# MODULIQ_POE_SPI.net
KiCad netlist of a schematic drawn in Altium Designer
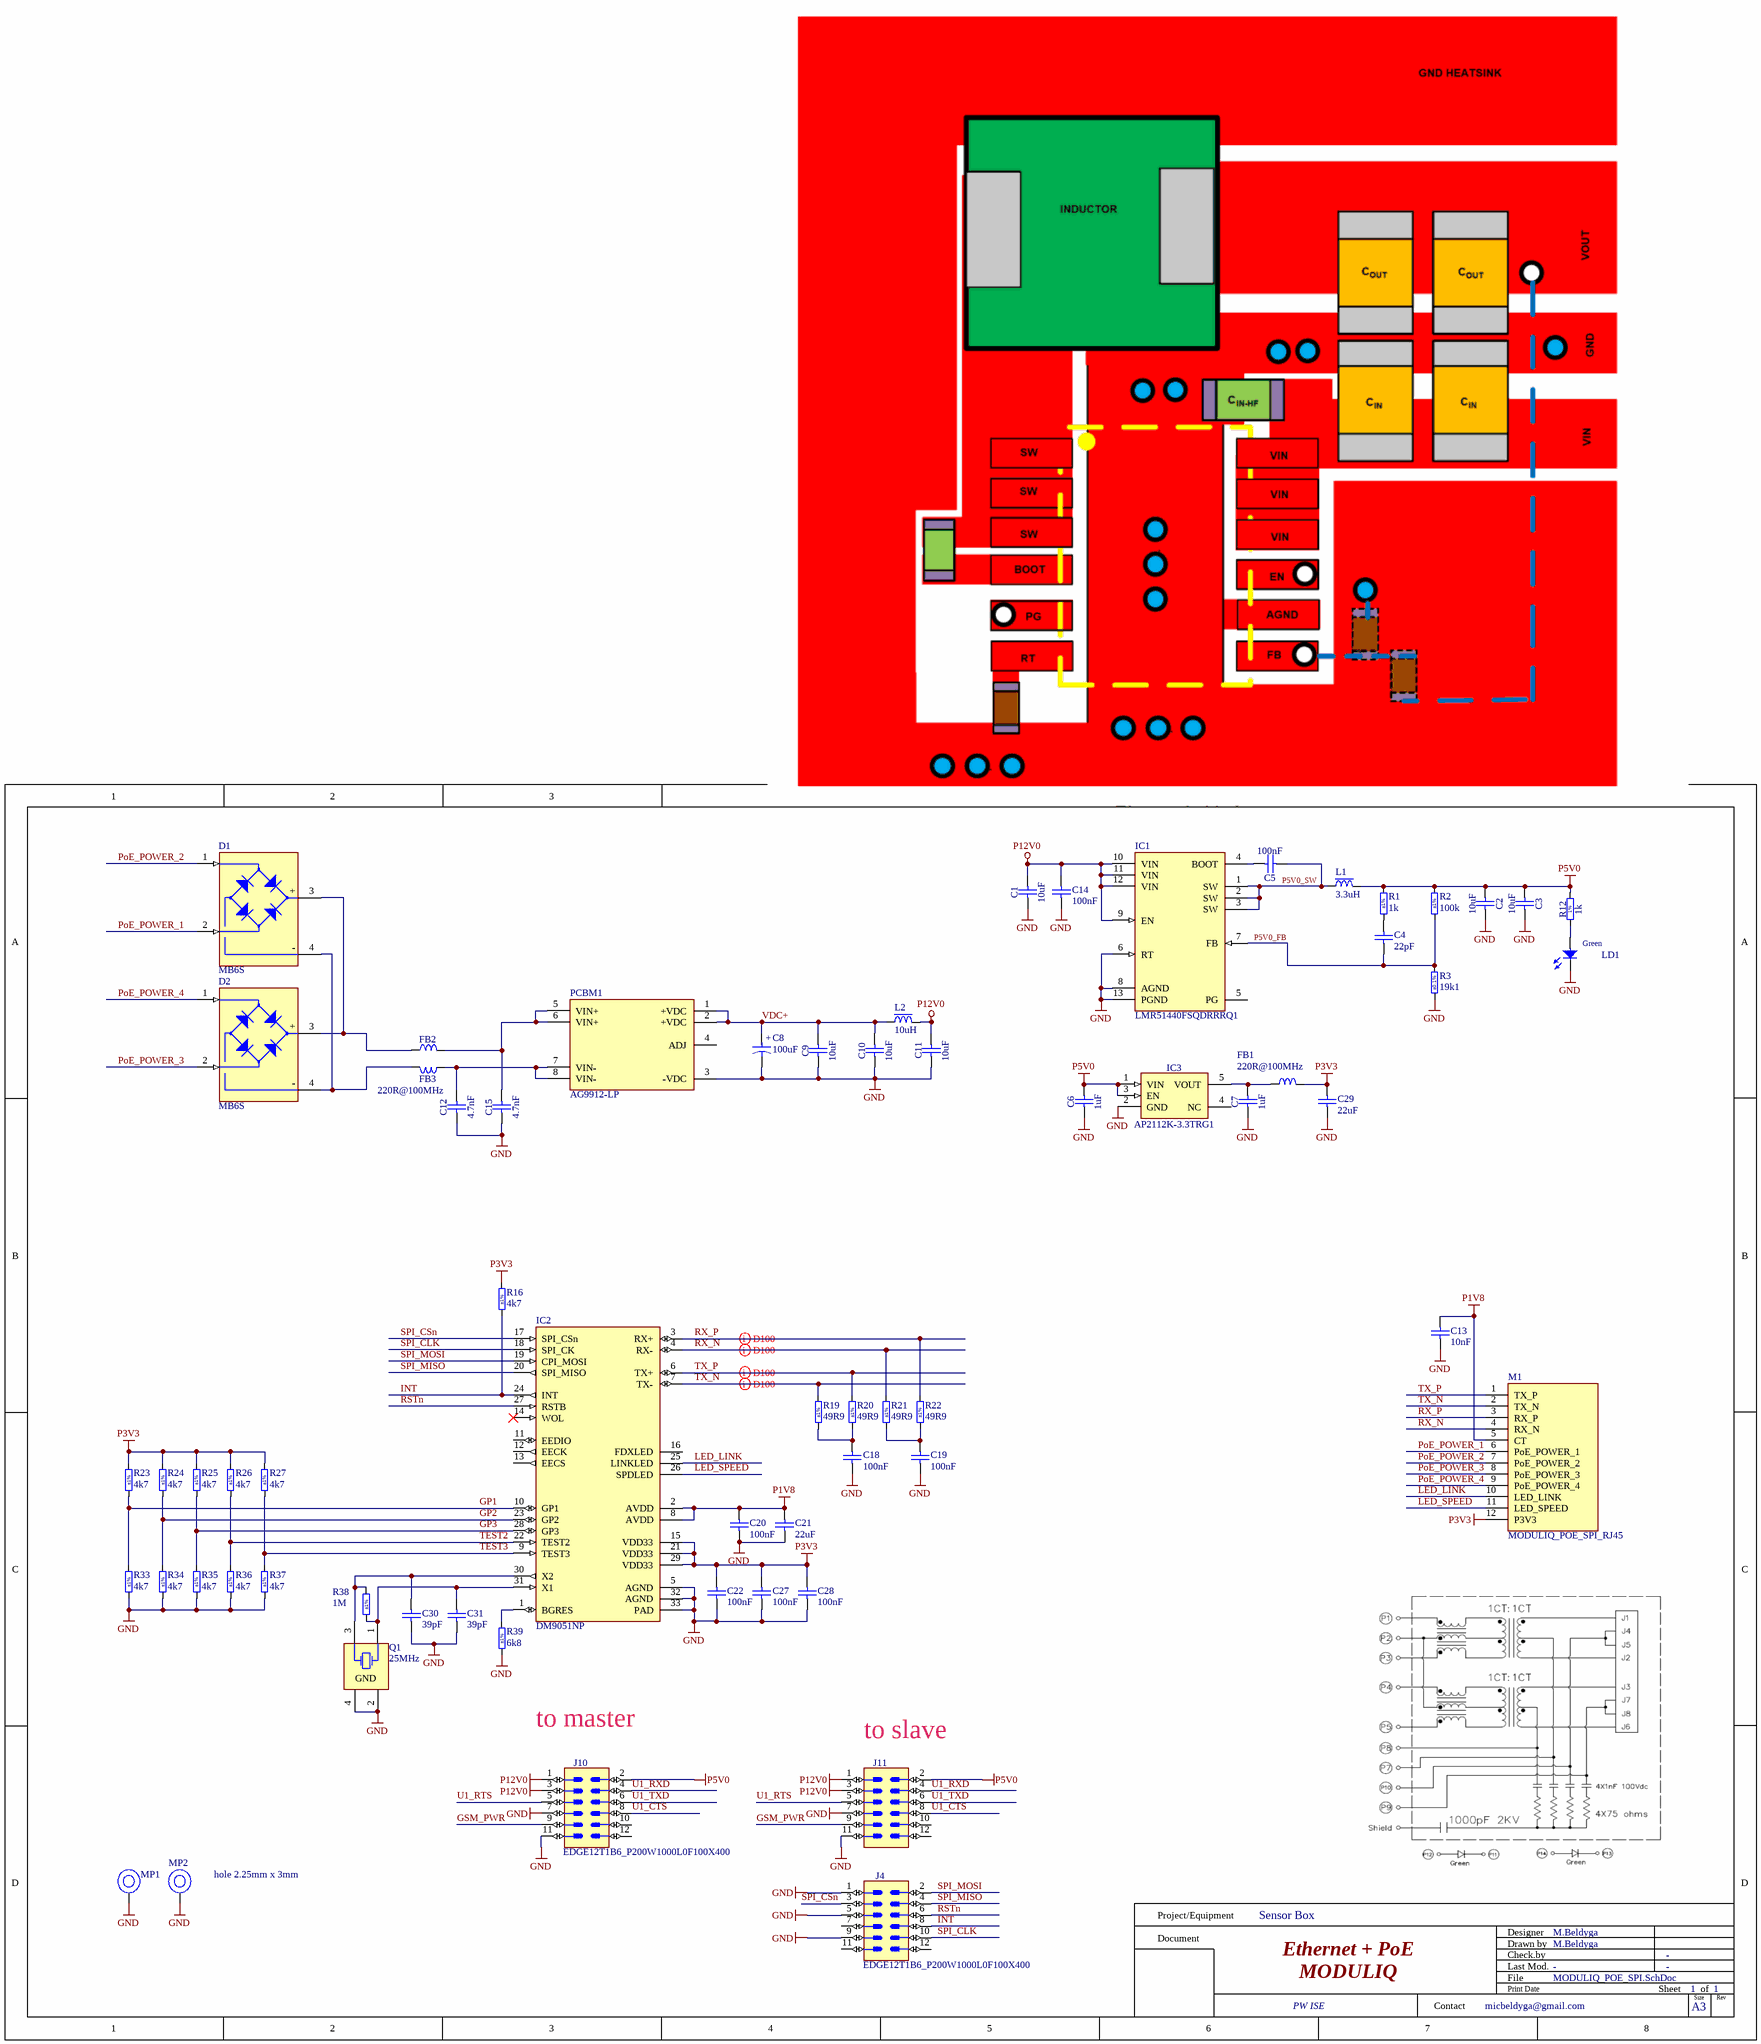
[diagram p0: MODULIQ_POE_SPI.SchDoc]

(export (version "E")
  (design (tool "Eeschema 10.0.6"))
  (components
    (comp (ref "C1")
      (value "10uF")
      (footprint "CAPC2012X135N")
      (description "Non-polarised capacitor")
      (fields
        (field (name "PART NUMBER") "CC0805_10UF_16V_10%_X5R")
        (field (name "VOLTAGE") "16V")
        (field (name "AUTHOR") "CERN DEM JLC")
      )
      (libsource (lib "Capacitors") (part "Capacitor - non polarized"))
    )
    (comp (ref "C2")
      (value "10uF")
      (footprint "CAPC2012X135N")
      (description "Non-polarised capacitor")
      (fields
        (field (name "PART NUMBER") "CC0805_10UF_16V_10%_X5R")
        (field (name "VOLTAGE") "16V")
        (field (name "AUTHOR") "CERN DEM JLC")
      )
      (libsource (lib "Capacitors") (part "Capacitor - non polarized"))
    )
    (comp (ref "C3")
      (value "10uF")
      (footprint "CAPC2012X135N")
      (description "Non-polarised capacitor")
      (fields
        (field (name "PART NUMBER") "CC0805_10UF_16V_10%_X5R")
        (field (name "VOLTAGE") "16V")
        (field (name "AUTHOR") "CERN DEM JLC")
      )
      (libsource (lib "Capacitors") (part "Capacitor - non polarized"))
    )
    (comp (ref "C4")
      (value "22pF")
      (footprint "CAPC1005X55N")
      (description "Non-polarised capacitor")
      (fields
        (field (name "PART NUMBER") "CC0402_22PF_50V_5%_C0G")
        (field (name "VOLTAGE") "50V")
        (field (name "AUTHOR") "CERN DEM JLC")
      )
      (libsource (lib "Capacitors") (part "Capacitor - non polarized"))
    )
    (comp (ref "C5")
      (value "100nF")
      (footprint "CAPC1005X55N")
      (description "Non-polarised capacitor")
      (fields
        (field (name "PART NUMBER") "CC0402_100NF_16V_10%_X5R")
        (field (name "VOLTAGE") "16V")
        (field (name "AUTHOR") "CERN DEM JLC")
      )
      (libsource (lib "Capacitors") (part "Capacitor - non polarized"))
    )
    (comp (ref "C6")
      (value "1uF")
      (footprint "CAPC1005X55N")
      (description "Non-polarised capacitor")
      (fields
        (field (name "PART NUMBER") "CC0402_1UF_16V_10%_X5R")
        (field (name "VOLTAGE") "16V")
        (field (name "AUTHOR") "CERN DEM JLC")
      )
      (libsource (lib "Capacitors") (part "Capacitor - non polarized"))
    )
    (comp (ref "C7")
      (value "1uF")
      (footprint "CAPC1005X55N")
      (description "Non-polarised capacitor")
      (fields
        (field (name "PART NUMBER") "CC0402_1UF_16V_10%_X5R")
        (field (name "VOLTAGE") "16V")
        (field (name "AUTHOR") "CERN DEM JLC")
      )
      (libsource (lib "Capacitors") (part "Capacitor - non polarized"))
    )
    (comp (ref "C8")
      (value "100uF")
      (footprint "CAPMP7343X430N")
      (description "Polarised capacitor")
      (fields
        (field (name "PART NUMBER") "CTE7343-43_100UF_25V_10%_LESR0150")
        (field (name "VOLTAGE") "25V")
        (field (name "AUTHOR") "CERN DEM JLC")
      )
      (libsource (lib "Capacitors") (part "Capacitor - polarized"))
    )
    (comp (ref "C9")
      (value "10uF")
      (footprint "CAPC2012X135N")
      (description "Non-polarised capacitor")
      (fields
        (field (name "PART NUMBER") "CC0805_10UF_16V_10%_X5R")
        (field (name "VOLTAGE") "16V")
        (field (name "AUTHOR") "CERN DEM JLC")
      )
      (libsource (lib "Capacitors") (part "Capacitor - non polarized"))
    )
    (comp (ref "C10")
      (value "10uF")
      (footprint "CAPC2012X135N")
      (description "Non-polarised capacitor")
      (fields
        (field (name "PART NUMBER") "CC0805_10UF_16V_10%_X5R")
        (field (name "VOLTAGE") "16V")
        (field (name "AUTHOR") "CERN DEM JLC")
      )
      (libsource (lib "Capacitors") (part "Capacitor - non polarized"))
    )
    (comp (ref "C11")
      (value "10uF")
      (footprint "CAPC2012X135N")
      (description "Non-polarised capacitor")
      (fields
        (field (name "PART NUMBER") "CC0805_10UF_16V_10%_X5R")
        (field (name "VOLTAGE") "16V")
        (field (name "AUTHOR") "CERN DEM JLC")
      )
      (libsource (lib "Capacitors") (part "Capacitor - non polarized"))
    )
    (comp (ref "C12")
      (value "4.7nF")
      (footprint "CAPC3216X140N")
      (description "Non-polarised capacitor")
      (fields
        (field (name "PART NUMBER") "CC1206_4.7NF_500V_10%_X7R")
        (field (name "VOLTAGE") "500V")
        (field (name "AUTHOR") "GK")
      )
      (libsource (lib "LIBRARY_SCH") (part "CAP_SMD_1206_4.7n_500V"))
    )
    (comp (ref "C13")
      (value "10nF")
      (footprint "CAPC1608X87N")
      (description "Non-polarised capacitor")
      (fields
        (field (name "PART NUMBER") "CC0603_10NF_50V_5%_C0G")
        (field (name "VOLTAGE") "50V")
        (field (name "AUTHOR") "CERN DEM JLC")
      )
      (libsource (lib "Capacitors") (part "Capacitor - non polarized"))
    )
    (comp (ref "C14")
      (value "100nF")
      (footprint "CAPC1005X55N")
      (description "Non-polarised capacitor")
      (fields
        (field (name "PART NUMBER") "CC0402_100NF_16V_10%_X5R")
        (field (name "VOLTAGE") "16V")
        (field (name "AUTHOR") "CERN DEM JLC")
      )
      (libsource (lib "Capacitors") (part "Capacitor - non polarized"))
    )
    (comp (ref "C15")
      (value "4.7nF")
      (footprint "CAPC3216X140N")
      (description "Non-polarised capacitor")
      (fields
        (field (name "PART NUMBER") "CC1206_4.7NF_500V_10%_X7R")
        (field (name "VOLTAGE") "500V")
        (field (name "AUTHOR") "GK")
      )
      (libsource (lib "LIBRARY_SCH") (part "CAP_SMD_1206_4.7n_500V"))
    )
    (comp (ref "C18")
      (value "100nF")
      (footprint "CAPC1005X55N")
      (description "Non-polarised capacitor")
      (fields
        (field (name "PART NUMBER") "CC0402_100NF_16V_10%_X5R")
        (field (name "VOLTAGE") "16V")
        (field (name "AUTHOR") "CERN DEM JLC")
      )
      (libsource (lib "Capacitors") (part "Capacitor - non polarized"))
    )
    (comp (ref "C19")
      (value "100nF")
      (footprint "CAPC1005X55N")
      (description "Non-polarised capacitor")
      (fields
        (field (name "PART NUMBER") "CC0402_100NF_16V_10%_X5R")
        (field (name "VOLTAGE") "16V")
        (field (name "AUTHOR") "CERN DEM JLC")
      )
      (libsource (lib "Capacitors") (part "Capacitor - non polarized"))
    )
    (comp (ref "C20")
      (value "100nF")
      (footprint "CAPC1005X55N")
      (description "Non-polarised capacitor")
      (fields
        (field (name "PART NUMBER") "CC0402_100NF_16V_10%_X5R")
        (field (name "VOLTAGE") "16V")
        (field (name "AUTHOR") "CERN DEM JLC")
      )
      (libsource (lib "Capacitors") (part "Capacitor - non polarized"))
    )
    (comp (ref "C21")
      (value "22uF")
      (footprint "CAPC1005X70N")
      (description "Non-polarised capacitor")
      (fields
        (field (name "PART NUMBER") "CC0402_22UF_6.3V_20%_X5R")
        (field (name "VOLTAGE") "6.3V")
        (field (name "AUTHOR") "CERN DEM HF")
      )
      (libsource (lib "Capacitors") (part "Capacitor - non polarized"))
    )
    (comp (ref "C22")
      (value "100nF")
      (footprint "CAPC1005X55N")
      (description "Non-polarised capacitor")
      (fields
        (field (name "PART NUMBER") "CC0402_100NF_16V_10%_X5R")
        (field (name "VOLTAGE") "16V")
        (field (name "AUTHOR") "CERN DEM JLC")
      )
      (libsource (lib "Capacitors") (part "Capacitor - non polarized"))
    )
    (comp (ref "C27")
      (value "100nF")
      (footprint "CAPC1005X55N")
      (description "Non-polarised capacitor")
      (fields
        (field (name "PART NUMBER") "CC0402_100NF_16V_10%_X5R")
        (field (name "VOLTAGE") "16V")
        (field (name "AUTHOR") "CERN DEM JLC")
      )
      (libsource (lib "Capacitors") (part "Capacitor - non polarized"))
    )
    (comp (ref "C28")
      (value "100nF")
      (footprint "CAPC1005X55N")
      (description "Non-polarised capacitor")
      (fields
        (field (name "PART NUMBER") "CC0402_100NF_16V_10%_X5R")
        (field (name "VOLTAGE") "16V")
        (field (name "AUTHOR") "CERN DEM JLC")
      )
      (libsource (lib "Capacitors") (part "Capacitor - non polarized"))
    )
    (comp (ref "C29")
      (value "22uF")
      (footprint "CAPC1005X70N")
      (description "Non-polarised capacitor")
      (fields
        (field (name "PART NUMBER") "CC0402_22UF_6.3V_20%_X5R")
        (field (name "VOLTAGE") "6.3V")
        (field (name "AUTHOR") "CERN DEM HF")
      )
      (libsource (lib "Capacitors") (part "Capacitor - non polarized"))
    )
    (comp (ref "C30")
      (value "39pF")
      (footprint "CAPC1005X55N")
      (description "Non-polarised capacitor")
      (fields
        (field (name "PART NUMBER") "CC0402_39PF_100V_5%_C0G_MURATA_GRM1555C2A390JA01")
        (field (name "VOLTAGE") "100V")
        (field (name "AUTHOR") "CERN DEM BC")
      )
      (libsource (lib "Capacitors") (part "Capacitor - non polarized"))
    )
    (comp (ref "C31")
      (value "39pF")
      (footprint "CAPC1005X55N")
      (description "Non-polarised capacitor")
      (fields
        (field (name "PART NUMBER") "CC0402_39PF_100V_5%_C0G_MURATA_GRM1555C2A390JA01")
        (field (name "VOLTAGE") "100V")
        (field (name "AUTHOR") "CERN DEM BC")
      )
      (libsource (lib "Capacitors") (part "Capacitor - non polarized"))
    )
    (comp (ref "D1")
      (value "MB6S")
      (footprint "SOIC254P665X290-4N")
      (description "Bridge Rectifier 1AC 2AC 3+ 4-")
      (fields
        (field (name "VOLTAGE") "600V")
        (field (name "POWER") "0.5A")
        (field (name "AUTHOR") "CERN DEM MR")
      )
      (libsource (lib "ICs And Semiconductors") (part "Bridge Rectifier 1AC 2AC 3+ 4-"))
    )
    (comp (ref "D2")
      (value "MB6S")
      (footprint "SOIC254P665X290-4N")
      (description "Bridge Rectifier 1AC 2AC 3+ 4-")
      (fields
        (field (name "VOLTAGE") "600V")
        (field (name "POWER") "0.5A")
        (field (name "AUTHOR") "CERN DEM MR")
      )
      (libsource (lib "ICs And Semiconductors") (part "Bridge Rectifier 1AC 2AC 3+ 4-"))
    )
    (comp (ref "FB1")
      (value "220R@100MHz")
      (footprint "INDC2012X105N")
      (description "Inductor")
      (fields
        (field (name "PART NUMBER") "IND0805_MURATA_BLM21PG221SN1D")
        (field (name "POWER") "2A")
        (field (name "AUTHOR") "CERN DEM JLC")
      )
      (libsource (lib "") (part "Inductor_1"))
    )
    (comp (ref "FB2")
      (value "220R@100MHz")
      (footprint "INDC2012X105N")
      (description "Inductor")
      (fields
        (field (name "PART NUMBER") "IND0805_MURATA_BLM21PG221SN1D")
        (field (name "POWER") "2A")
        (field (name "AUTHOR") "CERN DEM JLC")
      )
      (libsource (lib "Inductors & Transformers") (part "Inductor"))
    )
    (comp (ref "FB3")
      (value "220R@100MHz")
      (footprint "INDC2012X105N")
      (description "Inductor")
      (fields
        (field (name "PART NUMBER") "IND0805_MURATA_BLM21PG221SN1D")
        (field (name "POWER") "2A")
        (field (name "AUTHOR") "CERN DEM JLC")
      )
      (libsource (lib "") (part "Inductor_1"))
    )
    (comp (ref "IC1")
      (value "LMR51440FSQDRRRQ1")
      (footprint "SON50P300X80_HS-13N")
      (description "LMR51440-Q1 36V, 4A, Automotive, Synchronous Buck Converter With Low IQ")
      (fields
        (field (name "MANUFACTURER") "Texas Instruments")
        (field (name "ARENA PART NUMBER") "150-000055")
        (field (name "AUTHOR") "Michal Beldyga")
      )
      (libsource (lib "Semiconductors") (part "LMR514x0"))
    )
    (comp (ref "IC2")
      (value "DM9051NP")
      (footprint "QFN50P500X500X90_HS-33N_DM9051")
      (libsource (lib "mb") (part "DM9051NP"))
    )
    (comp (ref "IC3")
      (value "AP2112K-3.3TRG1")
      (footprint "SOT95P285X140-5N")
      (description "600mA CMOS Low Dropout Linear Regulator with Enable")
      (fields
        (field (name "MANUFACTURER") "DIODES INCORPORATED")
        (field (name "MANUFACTURER PART NUMBER") "AP2112K-3.3")
        (field (name "AUTHOR") "CERN DEM MR")
      )
      (libsource (lib "ICs And Semiconductors") (part "AP2112K"))
    )
    (comp (ref "J4")
      (value "~")
      (footprint "EDGE12T1B6_P200W1000L0F100X400")
      (description "PCB Edge Connector 12 (2x6)")
      (fields
        (field (name "PART NUMBER") "EDGE10T1B6_P200W1000L0F100X400")
        (field (name "AUTHOR") "CERN DEM MR")
      )
      (libsource (lib "Connectors") (part "PCB Edge Connector 12 (2x6)"))
    )
    (comp (ref "J10")
      (value "~")
      (footprint "EDGE12T1B6_P200W1000L0F100X400")
      (description "PCB Edge Connector 12 (2x6)")
      (fields
        (field (name "PART NUMBER") "EDGE10T1B6_P200W1000L0F100X400")
        (field (name "AUTHOR") "CERN DEM MR")
      )
      (libsource (lib "Connectors") (part "PCB Edge Connector 12 (2x6)"))
    )
    (comp (ref "J11")
      (value "~")
      (footprint "EDGE12T5B10_P200W1000L0F100X400")
      (description "PCB Edge Connector 12 (2x6)")
      (fields (field (name "PART NUMBER") "EDGE12T5B10_P200W1000L0F100X400") (field (name "AUTHOR") "GK"))
      (libsource (lib "Connectors") (part "PCB Edge Connector 12 (2x6) R"))
    )
    (comp (ref "L1")
      (value "3.3uH")
      (footprint "IND_COILCRAFT_XAL4030")
      (description "Inductor With Core")
      (fields
        (field (name "PART NUMBER") "IND_3.3UH_20%_COILCRAFT_XAL4030")
        (field (name "POWER") "5A")
        (field (name "AUTHOR") "CERN DEM BC")
      )
      (libsource (lib "Inductors & Transformers") (part "Inductor With Magnetic core"))
    )
    (comp (ref "L2")
      (value "10uH")
      (footprint "IND_MURATA-PS_8400")
      (description "Inductor With Core")
      (fields
        (field (name "PART NUMBER") "IND_10UH_10%_MURATA-PS_8400")
        (field (name "POWER") "950mA")
        (field (name "AUTHOR") "CERN DEM JLC")
      )
      (libsource (lib "Inductors & Transformers") (part "Inductor With Magnetic core"))
    )
    (comp (ref "LD1")
      (value "Green")
      (footprint "LED_KINGBRIGHT_KP-1608CGCK")
      (description "LED Green 1C 2A")
      (fields
        (field (name "PART NUMBER") "LED_KINGBRIGHT_KP-1608CGCK")
        (field (name "MANUFACTURER") "KINGBRIGHT")
        (field (name "AUTHOR") "CERN DEM HF")
      )
      (libsource (lib "ICs And Semiconductors") (part "LED Green 1C 2A"))
    )
    (comp (ref "M1")
      (value "MODULIQ_POE_SPI_RJ45")
      (footprint "MODULIQ_POE_SPI_RJ45")
      (description "MODULIQ POE SPI RJ45 module")
      (libsource (lib "mb") (part "MODULIQ_POE_SPI_RJ45"))
    )
    (comp (ref "MP1")
      (value "M1.6 x 3mm")
      (footprint "97730306330")
      (description "WA-SMSI SMT Steel Spacer with internal Thread Bottom closed, OD 3.3mm, M1.6 x 3mm")
      (fields
        (field (name "MANUFACTURER PART NUMBER") "97730306330R")
        (field (name "MANUFACTURER") "Wurth Elektronik")
      )
      (libsource (lib "Altium_WA-SMSI (rev22a)") (part "97730306330R"))
    )
    (comp (ref "MP2")
      (value "hole 2.25mm x 3mm")
      (footprint "9774030943")
      (description "WA-SMST SMT Steel Spacer, OD 4.35mm, hole 2.25mm x 3mm")
      (fields
        (field (name "MANUFACTURER PART NUMBER") "9774030943R")
        (field (name "MANUFACTURER") "Wurth Elektronik")
      )
      (libsource (lib "WE - Electromechanical Components") (part "Spacer"))
    )
    (comp (ref "PCBM1")
      (value "AG9912-LP")
      (footprint "Ag9900LP")
      (description "Low Profile IEEE802.3 af PoE Module - 12V")
      (fields (field (name "MANUFACTURER") "Silvertel"))
      (libsource (lib "mb") (part "AG9912-LP"))
    )
    (comp (ref "Q1")
      (value "25MHz")
      (footprint "XTAL_EPSON_TSX-3225")
      (description "Crystal 4 pins 1=XTAL Control 2=GND3=XTAL 4=GND")
      (fields
        (field (name "PART NUMBER") "XTAL_25MHZ_EPSON_TSX-3225 25.0000MF10Z-AC")
        (field (name "MANUFACTURER") "EPSON")
        (field (name "AUTHOR") "CERN DEM JLC")
      )
      (libsource (lib "ICs And Semiconductors") (part "Quartz Crystal 1X 2GND 3X 4GND"))
    )
    (comp (ref "R1")
      (value "1k")
      (footprint "RESC1005X40N")
      (description "Resistor - 1%")
      (fields
        (field (name "TOLERANCE") "±1%")
        (field (name "PART NUMBER") "R0402_1K_1%_0.0625W_100PPM")
        (field (name "POWER") "0.0625W")
        (field (name "AUTHOR") "CERN DEM JLC")
      )
      (libsource (lib "Resistors") (part "Resistor - 1%"))
    )
    (comp (ref "R2")
      (value "100k")
      (footprint "RESC1005X40N")
      (description "Resistor - 1%")
      (fields
        (field (name "TOLERANCE") "±1%")
        (field (name "PART NUMBER") "R0402_100K_1%_0.0625W_100PPM")
        (field (name "POWER") "0.0625W")
        (field (name "AUTHOR") "CERN DEM JLC")
      )
      (libsource (lib "Resistors") (part "Resistor - 1%"))
    )
    (comp (ref "R3")
      (value "19k1")
      (footprint "RESC1005X35N")
      (description "Resistor - 0.1%")
      (fields
        (field (name "TOLERANCE") "±0.1%")
        (field (name "PART NUMBER") "R0402_19K1_0.1%_0.063W_25PPM")
        (field (name "POWER") "0.063W")
        (field (name "AUTHOR") "CERN DEM MR")
      )
      (libsource (lib "Resistors") (part "Resistor - 0.1%"))
    )
    (comp (ref "R12")
      (value "1k")
      (footprint "RESC1005X40N")
      (description "Resistor - 1%")
      (fields
        (field (name "PART NUMBER") "R0402_1K_1%_0.0625W_100PPM")
        (field (name "POWER") "0.0625W")
        (field (name "AUTHOR") "CERN DEM JLC")
      )
      (libsource (lib "Resistors") (part "Resistor - 1%"))
    )
    (comp (ref "R16")
      (value "4k7")
      (footprint "RESC1005X40N")
      (description "Resistor - 1%")
      (fields
        (field (name "TOLERANCE") "±1%")
        (field (name "PART NUMBER") "R0402_4K7_1%_0.0625W_100PPM")
        (field (name "POWER") "0.0625W")
        (field (name "AUTHOR") "CERN DEM JLC")
      )
      (libsource (lib "Resistors") (part "Resistor - 1%"))
    )
    (comp (ref "R19")
      (value "49R9")
      (footprint "RESC1005X40N")
      (description "Resistor - 1%")
      (fields
        (field (name "TOLERANCE") "±1%")
        (field (name "PART NUMBER") "R0402_49R9_1%_0.0625W_100PPM")
        (field (name "POWER") "0.0625W")
        (field (name "AUTHOR") "CERN DEM JLC")
      )
      (libsource (lib "Resistors") (part "Resistor - 1%"))
    )
    (comp (ref "R20")
      (value "49R9")
      (footprint "RESC1005X40N")
      (description "Resistor - 1%")
      (fields
        (field (name "TOLERANCE") "±1%")
        (field (name "PART NUMBER") "R0402_49R9_1%_0.0625W_100PPM")
        (field (name "POWER") "0.0625W")
        (field (name "AUTHOR") "CERN DEM JLC")
      )
      (libsource (lib "Resistors") (part "Resistor - 1%"))
    )
    (comp (ref "R21")
      (value "49R9")
      (footprint "RESC1005X40N")
      (description "Resistor - 1%")
      (fields
        (field (name "TOLERANCE") "±1%")
        (field (name "PART NUMBER") "R0402_49R9_1%_0.0625W_100PPM")
        (field (name "POWER") "0.0625W")
        (field (name "AUTHOR") "CERN DEM JLC")
      )
      (libsource (lib "Resistors") (part "Resistor - 1%"))
    )
    (comp (ref "R22")
      (value "49R9")
      (footprint "RESC1005X40N")
      (description "Resistor - 1%")
      (fields
        (field (name "TOLERANCE") "±1%")
        (field (name "PART NUMBER") "R0402_49R9_1%_0.0625W_100PPM")
        (field (name "POWER") "0.0625W")
        (field (name "AUTHOR") "CERN DEM JLC")
      )
      (libsource (lib "Resistors") (part "Resistor - 1%"))
    )
    (comp (ref "R23")
      (value "4k7")
      (footprint "RESC1005X40N")
      (description "Resistor - 1%")
      (fields
        (field (name "TOLERANCE") "±1%")
        (field (name "PART NUMBER") "R0402_4K7_1%_0.0625W_100PPM")
        (field (name "POWER") "0.0625W")
        (field (name "AUTHOR") "CERN DEM JLC")
      )
      (libsource (lib "Resistors") (part "Resistor - 1%"))
    )
    (comp (ref "R24")
      (value "4k7")
      (footprint "RESC1005X40N")
      (description "Resistor - 1%")
      (fields
        (field (name "TOLERANCE") "±1%")
        (field (name "PART NUMBER") "R0402_4K7_1%_0.0625W_100PPM")
        (field (name "POWER") "0.0625W")
        (field (name "AUTHOR") "CERN DEM JLC")
      )
      (libsource (lib "Resistors") (part "Resistor - 1%"))
    )
    (comp (ref "R25")
      (value "4k7")
      (footprint "RESC1005X40N")
      (description "Resistor - 1%")
      (fields
        (field (name "TOLERANCE") "±1%")
        (field (name "PART NUMBER") "R0402_4K7_1%_0.0625W_100PPM")
        (field (name "POWER") "0.0625W")
        (field (name "AUTHOR") "CERN DEM JLC")
      )
      (libsource (lib "Resistors") (part "Resistor - 1%"))
    )
    (comp (ref "R26")
      (value "4k7")
      (footprint "RESC1005X40N")
      (description "Resistor - 1%")
      (fields
        (field (name "TOLERANCE") "±1%")
        (field (name "PART NUMBER") "R0402_4K7_1%_0.0625W_100PPM")
        (field (name "POWER") "0.0625W")
        (field (name "AUTHOR") "CERN DEM JLC")
      )
      (libsource (lib "Resistors") (part "Resistor - 1%"))
    )
    (comp (ref "R27")
      (value "4k7")
      (footprint "RESC1005X40N")
      (description "Resistor - 1%")
      (fields
        (field (name "TOLERANCE") "±1%")
        (field (name "PART NUMBER") "R0402_4K7_1%_0.0625W_100PPM")
        (field (name "POWER") "0.0625W")
        (field (name "AUTHOR") "CERN DEM JLC")
      )
      (libsource (lib "Resistors") (part "Resistor - 1%"))
    )
    (comp (ref "R33")
      (value "4k7")
      (footprint "RESC1005X40N")
      (description "Resistor - 1%")
      (fields
        (field (name "TOLERANCE") "±1%")
        (field (name "PART NUMBER") "R0402_4K7_1%_0.0625W_100PPM")
        (field (name "POWER") "0.0625W")
        (field (name "AUTHOR") "CERN DEM JLC")
      )
      (libsource (lib "Resistors") (part "Resistor - 1%"))
    )
    (comp (ref "R34")
      (value "4k7")
      (footprint "RESC1005X40N")
      (description "Resistor - 1%")
      (fields
        (field (name "TOLERANCE") "±1%")
        (field (name "PART NUMBER") "R0402_4K7_1%_0.0625W_100PPM")
        (field (name "POWER") "0.0625W")
        (field (name "AUTHOR") "CERN DEM JLC")
      )
      (libsource (lib "Resistors") (part "Resistor - 1%"))
    )
    (comp (ref "R35")
      (value "4k7")
      (footprint "RESC1005X40N")
      (description "Resistor - 1%")
      (fields
        (field (name "TOLERANCE") "±1%")
        (field (name "PART NUMBER") "R0402_4K7_1%_0.0625W_100PPM")
        (field (name "POWER") "0.0625W")
        (field (name "AUTHOR") "CERN DEM JLC")
      )
      (libsource (lib "Resistors") (part "Resistor - 1%"))
    )
    (comp (ref "R36")
      (value "4k7")
      (footprint "RESC1005X40N")
      (description "Resistor - 1%")
      (fields
        (field (name "TOLERANCE") "±1%")
        (field (name "PART NUMBER") "R0402_4K7_1%_0.0625W_100PPM")
        (field (name "POWER") "0.0625W")
        (field (name "AUTHOR") "CERN DEM JLC")
      )
      (libsource (lib "Resistors") (part "Resistor - 1%"))
    )
    (comp (ref "R37")
      (value "4k7")
      (footprint "RESC1005X40N")
      (description "Resistor - 1%")
      (fields
        (field (name "TOLERANCE") "±1%")
        (field (name "PART NUMBER") "R0402_4K7_1%_0.0625W_100PPM")
        (field (name "POWER") "0.0625W")
        (field (name "AUTHOR") "CERN DEM JLC")
      )
      (libsource (lib "Resistors") (part "Resistor - 1%"))
    )
    (comp (ref "R38")
      (value "1M")
      (footprint "RESC1005X40N")
      (description "Resistor - 1%")
      (fields
        (field (name "TOLERANCE") "±1%")
        (field (name "PART NUMBER") "R0402_1M_1%_0.0625W_100PPM")
        (field (name "POWER") "0.0625W")
        (field (name "AUTHOR") "CERN DEM JLC")
      )
      (libsource (lib "Resistors") (part "Resistor - 1%"))
    )
    (comp (ref "R39")
      (value "6k8")
      (footprint "RESC1005X40N")
      (description "Resistor - 1%")
      (fields
        (field (name "TOLERANCE") "±1%")
        (field (name "PART NUMBER") "R0402_6K8_1%_0.0625W_100PPM")
        (field (name "POWER") "0.0625W")
        (field (name "AUTHOR") "CERN DEM JLC")
      )
      (libsource (lib "Resistors") (part "Resistor - 1%"))
    )
  )
  (nets
    (net (code "1") (name "/GP1") (class "Default")
      (node (ref "IC2") (pin "10") (pinfunction "GP1_10") (pintype "bidirectional"))
      (node (ref "R23") (pin "1") (pinfunction "1_1") (pintype "passive"))
      (node (ref "R33") (pin "2") (pinfunction "2_2") (pintype "passive"))
    )
    (net (code "2") (name "/GP2") (class "Default")
      (node (ref "IC2") (pin "23") (pinfunction "GP2_23") (pintype "bidirectional"))
      (node (ref "R24") (pin "1") (pinfunction "1_1") (pintype "passive"))
      (node (ref "R34") (pin "2") (pinfunction "2_2") (pintype "passive"))
    )
    (net (code "3") (name "/GP3") (class "Default")
      (node (ref "IC2") (pin "28") (pinfunction "GP3_28") (pintype "bidirectional"))
      (node (ref "R25") (pin "1") (pinfunction "1_1") (pintype "passive"))
      (node (ref "R35") (pin "2") (pinfunction "2_2") (pintype "passive"))
    )
    (net (code "4") (name "/GSM_PWR") (class "Default")
      (node (ref "J10") (pin "9") (pinfunction "9_9") (pintype "bidirectional"))
      (node (ref "J11") (pin "9") (pinfunction "9_9") (pintype "bidirectional"))
    )
    (net (code "5") (name "/INT") (class "Default")
      (node (ref "IC2") (pin "24") (pinfunction "INT_24") (pintype "output"))
      (node (ref "J4") (pin "8") (pinfunction "8_8") (pintype "bidirectional"))
      (node (ref "R16") (pin "1") (pinfunction "1_1") (pintype "passive"))
    )
    (net (code "6") (name "/LED_LINK") (class "Default")
      (node (ref "IC2") (pin "25") (pinfunction "LINKLED_25") (pintype "open_collector"))
      (node (ref "M1") (pin "10") (pinfunction "LED_LINK_10") (pintype "passive"))
    )
    (net (code "7") (name "/LED_SPEED") (class "Default")
      (node (ref "IC2") (pin "26") (pinfunction "SPDLED_26") (pintype "open_collector"))
      (node (ref "M1") (pin "11") (pinfunction "LED_SPEED_11") (pintype "passive"))
    )
    (net (code "8") (name "/P5V0_FB") (class "Default")
      (node (ref "C4") (pin "1") (pinfunction "1_1") (pintype "passive"))
      (node (ref "IC1") (pin "7") (pinfunction "FB_7") (pintype "input"))
      (node (ref "R2") (pin "1") (pinfunction "1_1") (pintype "passive"))
      (node (ref "R3") (pin "2") (pinfunction "2_2") (pintype "passive"))
    )
    (net (code "9") (name "/P5V0_SW") (class "Default")
      (node (ref "C5") (pin "1") (pinfunction "1_1") (pintype "passive"))
      (node (ref "IC1") (pin "1") (pinfunction "SW_1") (pintype "power_in"))
      (node (ref "IC1") (pin "2") (pinfunction "SW_2") (pintype "power_in"))
      (node (ref "IC1") (pin "3") (pinfunction "SW_3") (pintype "power_in"))
      (node (ref "L1") (pin "1") (pinfunction "1_1") (pintype "passive"))
    )
    (net (code "10") (name "/PoE_POWER_1") (class "Default")
      (node (ref "D1") (pin "2") (pinfunction "AC_2") (pintype "input"))
      (node (ref "M1") (pin "6") (pinfunction "PoE_POWER_1_6") (pintype "passive"))
    )
    (net (code "11") (name "/PoE_POWER_2") (class "Default")
      (node (ref "D1") (pin "1") (pinfunction "AC_1") (pintype "input"))
      (node (ref "M1") (pin "7") (pinfunction "PoE_POWER_2_7") (pintype "passive"))
    )
    (net (code "12") (name "/PoE_POWER_3") (class "Default")
      (node (ref "D2") (pin "2") (pinfunction "AC_2") (pintype "input"))
      (node (ref "M1") (pin "8") (pinfunction "PoE_POWER_3_8") (pintype "passive"))
    )
    (net (code "13") (name "/PoE_POWER_4") (class "Default")
      (node (ref "D2") (pin "1") (pinfunction "AC_1") (pintype "input"))
      (node (ref "M1") (pin "9") (pinfunction "PoE_POWER_4_9") (pintype "passive"))
    )
    (net (code "14") (name "/RSTn") (class "Default")
      (node (ref "IC2") (pin "27") (pinfunction "RSTB_27") (pintype "input"))
      (node (ref "J4") (pin "6") (pinfunction "6_6") (pintype "bidirectional"))
    )
    (net (code "15") (name "/RX_N") (class "Default")
      (node (ref "IC2") (pin "4") (pinfunction "RX-_4") (pintype "bidirectional"))
      (node (ref "M1") (pin "4") (pinfunction "RX_N_4") (pintype "passive"))
      (node (ref "R21") (pin "2") (pinfunction "2_2") (pintype "passive"))
    )
    (net (code "16") (name "/RX_P") (class "Default")
      (node (ref "IC2") (pin "3") (pinfunction "RX+_3") (pintype "bidirectional"))
      (node (ref "M1") (pin "3") (pinfunction "RX_P_3") (pintype "passive"))
      (node (ref "R22") (pin "2") (pinfunction "2_2") (pintype "passive"))
    )
    (net (code "17") (name "/SPI_CLK") (class "Default")
      (node (ref "IC2") (pin "18") (pinfunction "SPI_CK_18") (pintype "input"))
      (node (ref "J4") (pin "10") (pinfunction "10_10") (pintype "bidirectional"))
    )
    (net (code "18") (name "/SPI_CSn") (class "Default")
      (node (ref "IC2") (pin "17") (pinfunction "SPI_CSn_17") (pintype "input"))
      (node (ref "J4") (pin "3") (pinfunction "3_3") (pintype "bidirectional"))
    )
    (net (code "19") (name "/SPI_MISO") (class "Default")
      (node (ref "IC2") (pin "20") (pinfunction "SPI_MISO_20") (pintype "output"))
      (node (ref "J4") (pin "4") (pinfunction "4_4") (pintype "bidirectional"))
    )
    (net (code "20") (name "/SPI_MOSI") (class "Default")
      (node (ref "IC2") (pin "19") (pinfunction "CPI_MOSI_19") (pintype "input"))
      (node (ref "J4") (pin "2") (pinfunction "2_2") (pintype "bidirectional"))
    )
    (net (code "21") (name "/TEST2") (class "Default")
      (node (ref "IC2") (pin "22") (pinfunction "TEST2_22") (pintype "input"))
      (node (ref "R26") (pin "1") (pinfunction "1_1") (pintype "passive"))
      (node (ref "R36") (pin "2") (pinfunction "2_2") (pintype "passive"))
    )
    (net (code "22") (name "/TEST3") (class "Default")
      (node (ref "IC2") (pin "9") (pinfunction "TEST3_9") (pintype "input"))
      (node (ref "R27") (pin "1") (pinfunction "1_1") (pintype "passive"))
      (node (ref "R37") (pin "2") (pinfunction "2_2") (pintype "passive"))
    )
    (net (code "23") (name "/TX_N") (class "Default")
      (node (ref "IC2") (pin "7") (pinfunction "TX-_7") (pintype "bidirectional"))
      (node (ref "M1") (pin "2") (pinfunction "TX_N_2") (pintype "passive"))
      (node (ref "R19") (pin "2") (pinfunction "2_2") (pintype "passive"))
    )
    (net (code "24") (name "/TX_P") (class "Default")
      (node (ref "IC2") (pin "6") (pinfunction "TX+_6") (pintype "bidirectional"))
      (node (ref "M1") (pin "1") (pinfunction "TX_P_1") (pintype "passive"))
      (node (ref "R20") (pin "2") (pinfunction "2_2") (pintype "passive"))
    )
    (net (code "25") (name "/U1_CTS") (class "Default")
      (node (ref "J10") (pin "8") (pinfunction "8_8") (pintype "bidirectional"))
      (node (ref "J11") (pin "8") (pinfunction "8_8") (pintype "bidirectional"))
    )
    (net (code "26") (name "/U1_RTS") (class "Default")
      (node (ref "J10") (pin "5") (pinfunction "5_5") (pintype "bidirectional"))
      (node (ref "J11") (pin "5") (pinfunction "5_5") (pintype "bidirectional"))
    )
    (net (code "27") (name "/U1_RXD") (class "Default")
      (node (ref "J10") (pin "4") (pinfunction "4_4") (pintype "bidirectional"))
      (node (ref "J11") (pin "4") (pinfunction "4_4") (pintype "bidirectional"))
    )
    (net (code "28") (name "/U1_TXD") (class "Default")
      (node (ref "J10") (pin "6") (pinfunction "6_6") (pintype "bidirectional"))
      (node (ref "J11") (pin "6") (pinfunction "6_6") (pintype "bidirectional"))
    )
    (net (code "29") (name "/VDC+") (class "Default")
      (node (ref "C10") (pin "2") (pinfunction "2_2") (pintype "passive"))
      (node (ref "C8") (pin "1") (pinfunction "1_1") (pintype "passive"))
      (node (ref "C9") (pin "2") (pinfunction "2_2") (pintype "passive"))
      (node (ref "L2") (pin "1") (pinfunction "1_1") (pintype "passive"))
      (node (ref "PCBM1") (pin "1") (pinfunction "+VDC_1") (pintype "power_in"))
      (node (ref "PCBM1") (pin "2") (pinfunction "+VDC_2") (pintype "power_in"))
    )
    (net (code "30") (name "GND") (class "Default")
      (node (ref "C1") (pin "1") (pinfunction "1_1") (pintype "passive"))
      (node (ref "C10") (pin "1") (pinfunction "1_1") (pintype "passive"))
      (node (ref "C11") (pin "1") (pinfunction "1_1") (pintype "passive"))
      (node (ref "C12") (pin "1") (pinfunction "1_1") (pintype "passive"))
      (node (ref "C13") (pin "1") (pinfunction "1_1") (pintype "passive"))
      (node (ref "C14") (pin "1") (pinfunction "1_1") (pintype "passive"))
      (node (ref "C15") (pin "1") (pinfunction "1_1") (pintype "passive"))
      (node (ref "C18") (pin "1") (pinfunction "1_1") (pintype "passive"))
      (node (ref "C19") (pin "1") (pinfunction "1_1") (pintype "passive"))
      (node (ref "C2") (pin "2") (pinfunction "2_2") (pintype "passive"))
      (node (ref "C20") (pin "1") (pinfunction "1_1") (pintype "passive"))
      (node (ref "C21") (pin "1") (pinfunction "1_1") (pintype "passive"))
      (node (ref "C22") (pin "1") (pinfunction "1_1") (pintype "passive"))
      (node (ref "C27") (pin "1") (pinfunction "1_1") (pintype "passive"))
      (node (ref "C28") (pin "1") (pinfunction "1_1") (pintype "passive"))
      (node (ref "C29") (pin "1") (pinfunction "1_1") (pintype "passive"))
      (node (ref "C3") (pin "2") (pinfunction "2_2") (pintype "passive"))
      (node (ref "C30") (pin "1") (pinfunction "1_1") (pintype "passive"))
      (node (ref "C31") (pin "1") (pinfunction "1_1") (pintype "passive"))
      (node (ref "C6") (pin "1") (pinfunction "1_1") (pintype "passive"))
      (node (ref "C7") (pin "1") (pinfunction "1_1") (pintype "passive"))
      (node (ref "C8") (pin "2") (pinfunction "2_2") (pintype "passive"))
      (node (ref "C9") (pin "1") (pinfunction "1_1") (pintype "passive"))
      (node (ref "IC1") (pin "13") (pinfunction "PGND_13") (pintype "power_in"))
      (node (ref "IC1") (pin "6") (pinfunction "RT_6") (pintype "input"))
      (node (ref "IC1") (pin "8") (pinfunction "AGND_8") (pintype "power_in"))
      (node (ref "IC2") (pin "32") (pinfunction "AGND_32") (pintype "power_in"))
      (node (ref "IC2") (pin "33") (pinfunction "PAD_33") (pintype "power_in"))
      (node (ref "IC2") (pin "5") (pinfunction "AGND_5") (pintype "power_in"))
      (node (ref "IC3") (pin "2") (pinfunction "GND_2") (pintype "power_in"))
      (node (ref "J10") (pin "11") (pinfunction "11_11") (pintype "bidirectional"))
      (node (ref "J10") (pin "7") (pinfunction "7_7") (pintype "bidirectional"))
      (node (ref "J11") (pin "11") (pinfunction "11_11") (pintype "bidirectional"))
      (node (ref "J11") (pin "7") (pinfunction "7_7") (pintype "bidirectional"))
      (node (ref "J4") (pin "1") (pinfunction "1_1") (pintype "bidirectional"))
      (node (ref "J4") (pin "5") (pinfunction "5_5") (pintype "bidirectional"))
      (node (ref "J4") (pin "9") (pinfunction "9_9") (pintype "bidirectional"))
      (node (ref "LD1") (pin "1") (pinfunction "C_1") (pintype "passive"))
      (node (ref "MP1") (pin "1") (pinfunction "1_1") (pintype "passive"))
      (node (ref "MP2") (pin "1") (pinfunction "1_1") (pintype "passive"))
      (node (ref "PCBM1") (pin "3") (pinfunction "-VDC_3") (pintype "power_in"))
      (node (ref "Q1") (pin "2") (pinfunction "GND_2") (pintype "power_in"))
      (node (ref "Q1") (pin "4") (pinfunction "GND_4") (pintype "power_in"))
      (node (ref "R3") (pin "1") (pinfunction "1_1") (pintype "passive"))
      (node (ref "R33") (pin "1") (pinfunction "1_1") (pintype "passive"))
      (node (ref "R34") (pin "1") (pinfunction "1_1") (pintype "passive"))
      (node (ref "R35") (pin "1") (pinfunction "1_1") (pintype "passive"))
      (node (ref "R36") (pin "1") (pinfunction "1_1") (pintype "passive"))
      (node (ref "R37") (pin "1") (pinfunction "1_1") (pintype "passive"))
      (node (ref "R39") (pin "1") (pinfunction "1_1") (pintype "passive"))
    )
    (net (code "31") (name "Net-(C4-Pad2)") (class "Default")
      (node (ref "C4") (pin "2") (pinfunction "2_2") (pintype "passive"))
      (node (ref "R1") (pin "1") (pinfunction "1_1") (pintype "passive"))
    )
    (net (code "32") (name "Net-(C12-Pad2)") (class "Default")
      (node (ref "C12") (pin "2") (pinfunction "2_2") (pintype "passive"))
      (node (ref "FB3") (pin "1") (pinfunction "1_1") (pintype "passive"))
      (node (ref "PCBM1") (pin "7") (pinfunction "VIN-_7") (pintype "power_in"))
      (node (ref "PCBM1") (pin "8") (pinfunction "VIN-_8") (pintype "power_in"))
    )
    (net (code "33") (name "Net-(C15-Pad2)") (class "Default")
      (node (ref "C15") (pin "2") (pinfunction "2_2") (pintype "passive"))
      (node (ref "FB2") (pin "1") (pinfunction "1_1") (pintype "passive"))
      (node (ref "PCBM1") (pin "5") (pinfunction "VIN+_5") (pintype "power_in"))
      (node (ref "PCBM1") (pin "6") (pinfunction "VIN+_6") (pintype "power_in"))
    )
    (net (code "34") (name "Net-(C18-Pad2)") (class "Default")
      (node (ref "C18") (pin "2") (pinfunction "2_2") (pintype "passive"))
      (node (ref "R19") (pin "1") (pinfunction "1_1") (pintype "passive"))
      (node (ref "R20") (pin "1") (pinfunction "1_1") (pintype "passive"))
    )
    (net (code "35") (name "Net-(C19-Pad2)") (class "Default")
      (node (ref "C19") (pin "2") (pinfunction "2_2") (pintype "passive"))
      (node (ref "R21") (pin "1") (pinfunction "1_1") (pintype "passive"))
      (node (ref "R22") (pin "1") (pinfunction "1_1") (pintype "passive"))
    )
    (net (code "36") (name "Net-(D1-+)") (class "Default")
      (node (ref "D1") (pin "3") (pinfunction "+_3") (pintype "power_in"))
      (node (ref "D2") (pin "3") (pinfunction "+_3") (pintype "power_in"))
      (node (ref "FB2") (pin "2") (pinfunction "2_2") (pintype "passive"))
    )
    (net (code "37") (name "Net-(D1--)") (class "Default")
      (node (ref "D1") (pin "4") (pinfunction "-_4") (pintype "power_in"))
      (node (ref "D2") (pin "4") (pinfunction "-_4") (pintype "power_in"))
      (node (ref "FB3") (pin "2") (pinfunction "2_2") (pintype "passive"))
    )
    (net (code "38") (name "Net-(IC1-BOOT)") (class "Default")
      (node (ref "C5") (pin "2") (pinfunction "2_2") (pintype "passive"))
      (node (ref "IC1") (pin "4") (pinfunction "BOOT_4") (pintype "power_in"))
    )
    (net (code "39") (name "Net-(IC2-BGRES)") (class "Default")
      (node (ref "IC2") (pin "1") (pinfunction "BGRES_1") (pintype "bidirectional"))
      (node (ref "R39") (pin "2") (pinfunction "2_2") (pintype "passive"))
    )
    (net (code "40") (name "Net-(IC2-X1)") (class "Default")
      (node (ref "C31") (pin "2") (pinfunction "2_2") (pintype "passive"))
      (node (ref "IC2") (pin "31") (pinfunction "X1_31") (pintype "input"))
      (node (ref "Q1") (pin "1") (pinfunction "X_1") (pintype "passive"))
      (node (ref "R38") (pin "2") (pinfunction "2_2") (pintype "passive"))
    )
    (net (code "41") (name "Net-(IC2-X2)") (class "Default")
      (node (ref "C30") (pin "2") (pinfunction "2_2") (pintype "passive"))
      (node (ref "IC2") (pin "30") (pinfunction "X2_30") (pintype "output"))
      (node (ref "Q1") (pin "3") (pinfunction "X_3") (pintype "passive"))
      (node (ref "R38") (pin "1") (pinfunction "1_1") (pintype "passive"))
    )
    (net (code "42") (name "Net-(IC3-VOUT)") (class "Default")
      (node (ref "C7") (pin "2") (pinfunction "2_2") (pintype "passive"))
      (node (ref "FB1") (pin "1") (pinfunction "1_1") (pintype "passive"))
      (node (ref "IC3") (pin "5") (pinfunction "VOUT_5") (pintype "power_in"))
    )
    (net (code "43") (name "Net-(LD1-A)") (class "Default")
      (node (ref "LD1") (pin "2") (pinfunction "A_2") (pintype "passive"))
      (node (ref "R12") (pin "1") (pinfunction "1_1") (pintype "passive"))
    )
    (net (code "44") (name "P1V8") (class "Default")
      (node (ref "C13") (pin "2") (pinfunction "2_2") (pintype "passive"))
      (node (ref "C20") (pin "2") (pinfunction "2_2") (pintype "passive"))
      (node (ref "C21") (pin "2") (pinfunction "2_2") (pintype "passive"))
      (node (ref "IC2") (pin "2") (pinfunction "AVDD_2") (pintype "power_in"))
      (node (ref "IC2") (pin "8") (pinfunction "AVDD_8") (pintype "power_in"))
      (node (ref "M1") (pin "5") (pinfunction "CT_5") (pintype "passive"))
    )
    (net (code "45") (name "P3V3") (class "Default")
      (node (ref "C22") (pin "2") (pinfunction "2_2") (pintype "passive"))
      (node (ref "C27") (pin "2") (pinfunction "2_2") (pintype "passive"))
      (node (ref "C28") (pin "2") (pinfunction "2_2") (pintype "passive"))
      (node (ref "C29") (pin "2") (pinfunction "2_2") (pintype "passive"))
      (node (ref "FB1") (pin "2") (pinfunction "2_2") (pintype "passive"))
      (node (ref "IC2") (pin "15") (pinfunction "VDD33_15") (pintype "power_in"))
      (node (ref "IC2") (pin "21") (pinfunction "VDD33_21") (pintype "power_in"))
      (node (ref "IC2") (pin "29") (pinfunction "VDD33_29") (pintype "power_in"))
      (node (ref "M1") (pin "12") (pinfunction "P3V3_12") (pintype "passive"))
      (node (ref "R16") (pin "2") (pinfunction "2_2") (pintype "passive"))
      (node (ref "R23") (pin "2") (pinfunction "2_2") (pintype "passive"))
      (node (ref "R24") (pin "2") (pinfunction "2_2") (pintype "passive"))
      (node (ref "R25") (pin "2") (pinfunction "2_2") (pintype "passive"))
      (node (ref "R26") (pin "2") (pinfunction "2_2") (pintype "passive"))
      (node (ref "R27") (pin "2") (pinfunction "2_2") (pintype "passive"))
    )
    (net (code "46") (name "P5V0") (class "Default")
      (node (ref "C2") (pin "1") (pinfunction "1_1") (pintype "passive"))
      (node (ref "C3") (pin "1") (pinfunction "1_1") (pintype "passive"))
      (node (ref "C6") (pin "2") (pinfunction "2_2") (pintype "passive"))
      (node (ref "IC3") (pin "1") (pinfunction "VIN_1") (pintype "input"))
      (node (ref "IC3") (pin "3") (pinfunction "EN_3") (pintype "input"))
      (node (ref "J10") (pin "2") (pinfunction "2_2") (pintype "bidirectional"))
      (node (ref "J11") (pin "2") (pinfunction "2_2") (pintype "bidirectional"))
      (node (ref "L1") (pin "2") (pinfunction "2_2") (pintype "passive"))
      (node (ref "R1") (pin "2") (pinfunction "2_2") (pintype "passive"))
      (node (ref "R12") (pin "2") (pinfunction "2_2") (pintype "passive"))
      (node (ref "R2") (pin "2") (pinfunction "2_2") (pintype "passive"))
    )
    (net (code "47") (name "P12V0") (class "Default")
      (node (ref "C1") (pin "2") (pinfunction "2_2") (pintype "passive"))
      (node (ref "C11") (pin "2") (pinfunction "2_2") (pintype "passive"))
      (node (ref "C14") (pin "2") (pinfunction "2_2") (pintype "passive"))
      (node (ref "IC1") (pin "10") (pinfunction "VIN_10") (pintype "power_in"))
      (node (ref "IC1") (pin "11") (pinfunction "VIN_11") (pintype "power_in"))
      (node (ref "IC1") (pin "12") (pinfunction "VIN_12") (pintype "power_in"))
      (node (ref "IC1") (pin "9") (pinfunction "EN_9") (pintype "input"))
      (node (ref "J10") (pin "1") (pinfunction "1_1") (pintype "bidirectional"))
      (node (ref "J10") (pin "3") (pinfunction "3_3") (pintype "bidirectional"))
      (node (ref "J11") (pin "1") (pinfunction "1_1") (pintype "bidirectional"))
      (node (ref "J11") (pin "3") (pinfunction "3_3") (pintype "bidirectional"))
      (node (ref "L2") (pin "2") (pinfunction "2_2") (pintype "passive"))
    )
    (net (code "48") (name "unconnected-(IC1-PG-Pad5)") (class "Default")
      (node (ref "IC1") (pin "5") (pinfunction "PG_5") (pintype "open_collector"))
    )
    (net (code "49") (name "unconnected-(IC2-EECK-Pad12)") (class "Default")
      (node (ref "IC2") (pin "12") (pinfunction "EECK_12") (pintype "output"))
    )
    (net (code "50") (name "unconnected-(IC2-EECS-Pad13)") (class "Default")
      (node (ref "IC2") (pin "13") (pinfunction "EECS_13") (pintype "output"))
    )
    (net (code "51") (name "unconnected-(IC2-EEDIO-Pad11)") (class "Default")
      (node (ref "IC2") (pin "11") (pinfunction "EEDIO_11") (pintype "bidirectional"))
    )
    (net (code "52") (name "unconnected-(IC2-FDXLED-Pad16)") (class "Default")
      (node (ref "IC2") (pin "16") (pinfunction "FDXLED_16") (pintype "open_collector"))
    )
    (net (code "53") (name "unconnected-(IC2-WOL-Pad14)") (class "Default")
      (node (ref "IC2") (pin "14") (pinfunction "WOL_14") (pintype "input+no_connect"))
    )
    (net (code "54") (name "unconnected-(IC3-NC-Pad4)") (class "Default")
      (node (ref "IC3") (pin "4") (pinfunction "NC_4") (pintype "passive"))
    )
    (net (code "55") (name "unconnected-(J4-Pad7)") (class "Default")
      (node (ref "J4") (pin "7") (pinfunction "7_7") (pintype "bidirectional"))
    )
    (net (code "56") (name "unconnected-(J4-Pad11)") (class "Default")
      (node (ref "J4") (pin "11") (pinfunction "11_11") (pintype "bidirectional"))
    )
    (net (code "57") (name "unconnected-(J4-Pad12)") (class "Default")
      (node (ref "J4") (pin "12") (pinfunction "12_12") (pintype "bidirectional"))
    )
    (net (code "58") (name "unconnected-(J10-Pad10)") (class "Default")
      (node (ref "J10") (pin "10") (pinfunction "10_10") (pintype "bidirectional"))
    )
    (net (code "59") (name "unconnected-(J10-Pad12)") (class "Default")
      (node (ref "J10") (pin "12") (pinfunction "12_12") (pintype "bidirectional"))
    )
    (net (code "60") (name "unconnected-(J11-Pad10)") (class "Default")
      (node (ref "J11") (pin "10") (pinfunction "10_10") (pintype "bidirectional"))
    )
    (net (code "61") (name "unconnected-(J11-Pad12)") (class "Default")
      (node (ref "J11") (pin "12") (pinfunction "12_12") (pintype "bidirectional"))
    )
    (net (code "62") (name "unconnected-(PCBM1-ADJ-Pad4)") (class "Default")
      (node (ref "PCBM1") (pin "4") (pinfunction "ADJ_4") (pintype "passive"))
    )
  )
)
